# 454_stereo_mic_Rev020002.net
KiCad netlist of a schematic drawn in EAGLE
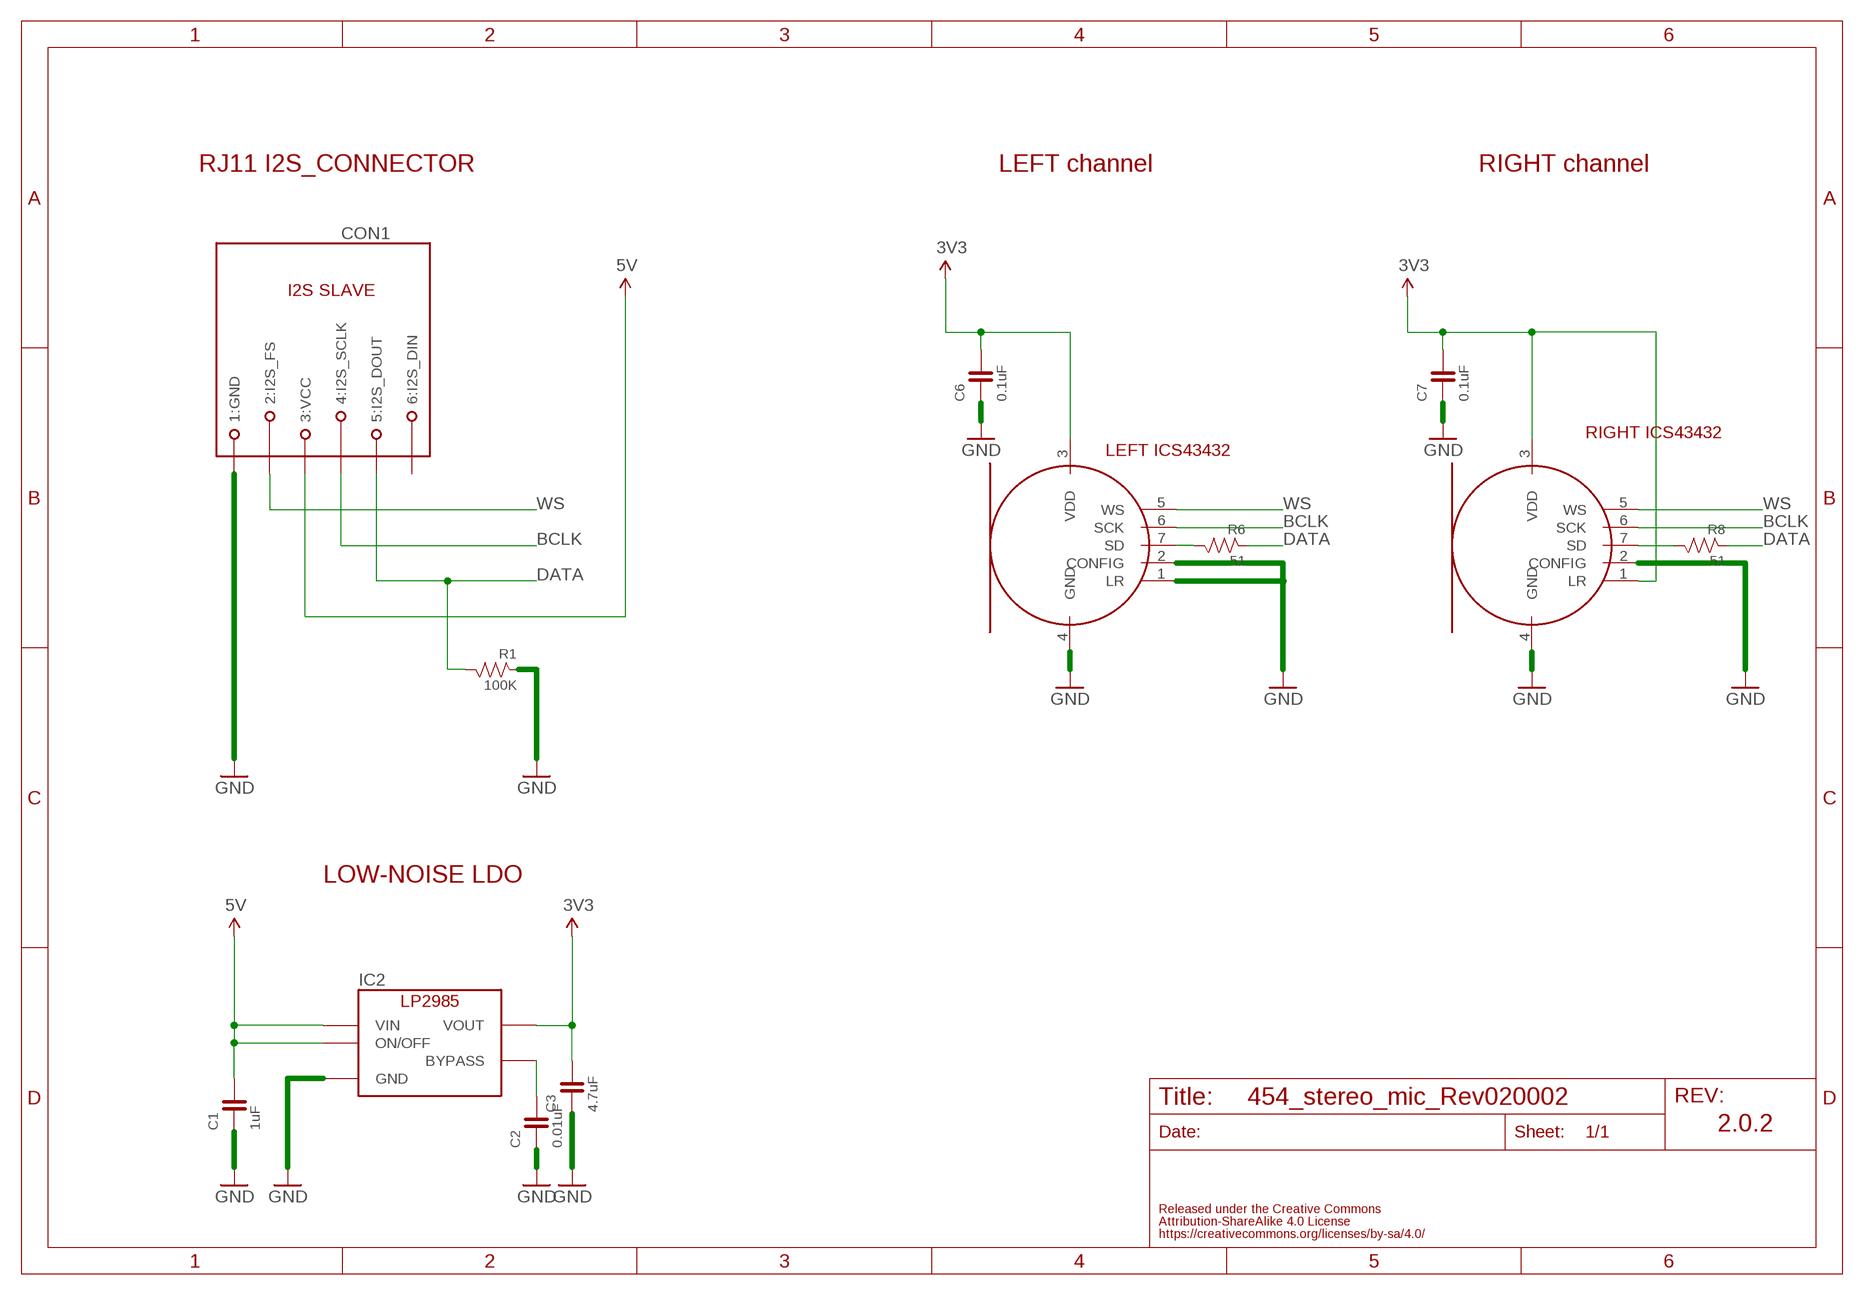
[diagram p0: schematic, sheet 1]

(export (version "E")
  (design (tool "Eeschema 10.0.6"))
  (components
    (comp (ref "C1")
      (value "1uF")
      (footprint "eagle-import:0603")
      (libsource (lib "eagle-import") (part "CAPACITOR-0603"))
    )
    (comp (ref "C2")
      (value "0.01uF")
      (footprint "eagle-import:0603")
      (libsource (lib "eagle-import") (part "CAPACITOR-0603"))
    )
    (comp (ref "C3")
      (value "4.7uF")
      (footprint "eagle-import:0603")
      (libsource (lib "eagle-import") (part "CAPACITOR-0603"))
    )
    (comp (ref "C6")
      (value "0.1uF")
      (footprint "eagle-import:0603")
      (libsource (lib "eagle-import") (part "CAPACITOR-0603"))
    )
    (comp (ref "C7")
      (value "0.1uF")
      (footprint "eagle-import:0603")
      (libsource (lib "eagle-import") (part "CAPACITOR-0603"))
    )
    (comp (ref "CON1")
      (value "MODULAR-JACK-6P-RJ11_I2S_SLAVE")
      (footprint "eagle-import:7002-6PXC-X")
      (libsource (lib "eagle-import") (part "MODULAR-JACK-6P-RJ11_I2S_SLAVE"))
    )
    (comp (ref "IC2")
      (value "LP2985-33DBV")
      (footprint "eagle-import:SOT-23-5")
      (libsource (lib "eagle-import") (part "LP2985-33DBV"))
    )
    (comp (ref "MIC_LEFT")
      (value "TDK-ICS43432")
      (footprint "eagle-import:TDK-ICS43432")
      (libsource (lib "eagle-import") (part "TDK-ICS43432"))
    )
    (comp (ref "MIC_RIGHT")
      (value "TDK-ICS43432")
      (footprint "eagle-import:TDK-ICS43432")
      (libsource (lib "eagle-import") (part "TDK-ICS43432"))
    )
    (comp (ref "R1")
      (value "100K")
      (footprint "eagle-import:0603")
      (libsource (lib "eagle-import") (part "RESISTOR-0603"))
    )
    (comp (ref "R6")
      (value "51")
      (footprint "eagle-import:0603")
      (libsource (lib "eagle-import") (part "RESISTOR-0603"))
    )
    (comp (ref "R8")
      (value "51")
      (footprint "eagle-import:0603")
      (libsource (lib "eagle-import") (part "RESISTOR-0603"))
    )
  )
  (nets
    (net (code "1") (name "/BCLK") (class "Default")
      (node (ref "CON1") (pin "4") (pinfunction "4:I2S_SCLK_4") (pintype "bidirectional"))
      (node (ref "MIC_LEFT") (pin "6") (pinfunction "SCK_6") (pintype "bidirectional"))
      (node (ref "MIC_RIGHT") (pin "6") (pinfunction "SCK_6") (pintype "bidirectional"))
    )
    (net (code "2") (name "/DATA") (class "Default")
      (node (ref "CON1") (pin "5") (pinfunction "5:I2S_DOUT_5") (pintype "output"))
      (node (ref "R1") (pin "2") (pinfunction "2_2") (pintype "bidirectional"))
      (node (ref "R6") (pin "1") (pinfunction "1_1") (pintype "bidirectional"))
      (node (ref "R8") (pin "1") (pinfunction "1_1") (pintype "bidirectional"))
    )
    (net (code "3") (name "/WS") (class "Default")
      (node (ref "CON1") (pin "2") (pinfunction "2:I2S_FS_2") (pintype "bidirectional"))
      (node (ref "MIC_LEFT") (pin "5") (pinfunction "WS_5") (pintype "bidirectional"))
      (node (ref "MIC_RIGHT") (pin "5") (pinfunction "WS_5") (pintype "bidirectional"))
    )
    (net (code "4") (name "3V3") (class "Default")
      (node (ref "C3") (pin "2") (pinfunction "2_2") (pintype "passive"))
      (node (ref "C6") (pin "2") (pinfunction "2_2") (pintype "passive"))
      (node (ref "C7") (pin "2") (pinfunction "2_2") (pintype "passive"))
      (node (ref "IC2") (pin "5") (pinfunction "VOUT_5") (pintype "output"))
      (node (ref "MIC_LEFT") (pin "3") (pinfunction "VDD_3") (pintype "bidirectional"))
      (node (ref "MIC_RIGHT") (pin "1") (pinfunction "LR_1") (pintype "bidirectional"))
      (node (ref "MIC_RIGHT") (pin "3") (pinfunction "VDD_3") (pintype "bidirectional"))
    )
    (net (code "5") (name "5V") (class "Default")
      (node (ref "C1") (pin "2") (pinfunction "2_2") (pintype "passive"))
      (node (ref "CON1") (pin "3") (pinfunction "3:VCC_3") (pintype "power_in"))
      (node (ref "IC2") (pin "1") (pinfunction "VIN_1") (pintype "input"))
      (node (ref "IC2") (pin "3") (pinfunction "ON/OFF_3") (pintype "input"))
    )
    (net (code "6") (name "GND") (class "Default")
      (node (ref "C1") (pin "1") (pinfunction "1_1") (pintype "passive"))
      (node (ref "C2") (pin "1") (pinfunction "1_1") (pintype "passive"))
      (node (ref "C3") (pin "1") (pinfunction "1_1") (pintype "passive"))
      (node (ref "C6") (pin "1") (pinfunction "1_1") (pintype "passive"))
      (node (ref "C7") (pin "1") (pinfunction "1_1") (pintype "passive"))
      (node (ref "CON1") (pin "1") (pinfunction "1:GND_1") (pintype "power_in"))
      (node (ref "IC2") (pin "2") (pinfunction "GND_2") (pintype "power_in"))
      (node (ref "MIC_LEFT") (pin "1") (pinfunction "LR_1") (pintype "bidirectional"))
      (node (ref "MIC_LEFT") (pin "2") (pinfunction "CONFIG_2") (pintype "bidirectional"))
      (node (ref "MIC_LEFT") (pin "4") (pinfunction "GND_4") (pintype "bidirectional"))
      (node (ref "MIC_RIGHT") (pin "2") (pinfunction "CONFIG_2") (pintype "bidirectional"))
      (node (ref "MIC_RIGHT") (pin "4") (pinfunction "GND_4") (pintype "bidirectional"))
      (node (ref "R1") (pin "1") (pinfunction "1_1") (pintype "bidirectional"))
    )
    (net (code "7") (name "Net-(IC2-BYPASS)") (class "Default")
      (node (ref "C2") (pin "2") (pinfunction "2_2") (pintype "passive"))
      (node (ref "IC2") (pin "4") (pinfunction "BYPASS_4") (pintype "bidirectional"))
    )
    (net (code "8") (name "Net-(MIC_LEFT-SD)") (class "Default")
      (node (ref "MIC_LEFT") (pin "7") (pinfunction "SD_7") (pintype "bidirectional"))
      (node (ref "R6") (pin "2") (pinfunction "2_2") (pintype "bidirectional"))
    )
    (net (code "9") (name "Net-(MIC_RIGHT-SD)") (class "Default")
      (node (ref "MIC_RIGHT") (pin "7") (pinfunction "SD_7") (pintype "bidirectional"))
      (node (ref "R8") (pin "2") (pinfunction "2_2") (pintype "bidirectional"))
    )
    (net (code "10") (name "unconnected-(CON1-6:I2S_DIN-Pad6)") (class "Default")
      (node (ref "CON1") (pin "6") (pinfunction "6:I2S_DIN_6") (pintype "input"))
    )
  )
)
